# VU_Meter_1inchx3inches_V1_0.net
KiCad netlist of a schematic drawn in EAGLE
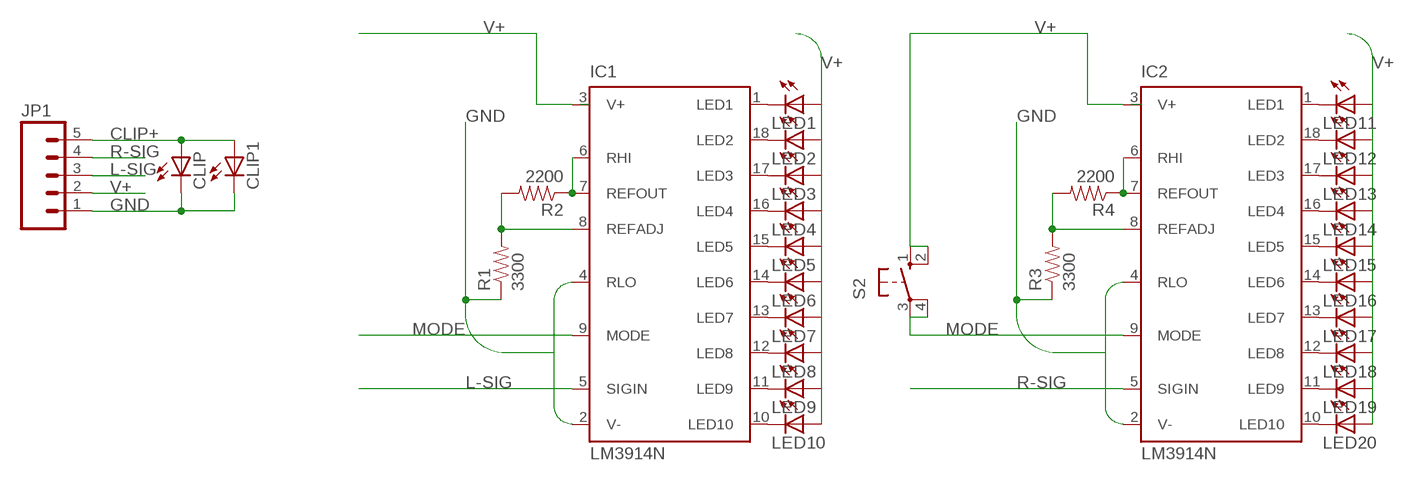
[diagram p0: schematic, sheet 1]

(export (version "E")
  (design (tool "Eeschema 10.0.6"))
  (components
    (comp (ref "CLIP")
      (value "LED5MM")
      (footprint "eagle-import:LED5MM")
      (libsource (lib "eagle-import") (part "LED5MM"))
    )
    (comp (ref "CLIP1")
      (value "LED5MM")
      (footprint "eagle-import:LED5MM")
      (libsource (lib "eagle-import") (part "LED5MM"))
    )
    (comp (ref "IC1")
      (value "LM3914N")
      (footprint "eagle-import:DIL18")
      (libsource (lib "eagle-import") (part "LM391N4"))
    )
    (comp (ref "IC2")
      (value "LM3914N")
      (footprint "eagle-import:DIL18")
      (libsource (lib "eagle-import") (part "LM391N4"))
    )
    (comp (ref "JP1")
      (value "M05SMD2")
      (footprint "eagle-import:1X05-1MM-RA")
      (libsource (lib "eagle-import") (part "M05SMD2"))
    )
    (comp (ref "LED1")
      (value "LED5MM")
      (footprint "eagle-import:LED5MM")
      (libsource (lib "eagle-import") (part "LED5MM"))
    )
    (comp (ref "LED2")
      (value "LED5MM")
      (footprint "eagle-import:LED5MM")
      (libsource (lib "eagle-import") (part "LED5MM"))
    )
    (comp (ref "LED3")
      (value "LED5MM")
      (footprint "eagle-import:LED5MM")
      (libsource (lib "eagle-import") (part "LED5MM"))
    )
    (comp (ref "LED4")
      (value "LED5MM")
      (footprint "eagle-import:LED5MM")
      (libsource (lib "eagle-import") (part "LED5MM"))
    )
    (comp (ref "LED5")
      (value "LED5MM")
      (footprint "eagle-import:LED5MM")
      (libsource (lib "eagle-import") (part "LED5MM"))
    )
    (comp (ref "LED6")
      (value "LED5MM")
      (footprint "eagle-import:LED5MM")
      (libsource (lib "eagle-import") (part "LED5MM"))
    )
    (comp (ref "LED7")
      (value "LED5MM")
      (footprint "eagle-import:LED5MM")
      (libsource (lib "eagle-import") (part "LED5MM"))
    )
    (comp (ref "LED8")
      (value "LED5MM")
      (footprint "eagle-import:LED5MM")
      (libsource (lib "eagle-import") (part "LED5MM"))
    )
    (comp (ref "LED9")
      (value "LED5MM")
      (footprint "eagle-import:LED5MM")
      (libsource (lib "eagle-import") (part "LED5MM"))
    )
    (comp (ref "LED10")
      (value "LED5MM")
      (footprint "eagle-import:LED5MM")
      (libsource (lib "eagle-import") (part "LED5MM"))
    )
    (comp (ref "LED11")
      (value "LED5MM")
      (footprint "eagle-import:LED5MM")
      (libsource (lib "eagle-import") (part "LED5MM"))
    )
    (comp (ref "LED12")
      (value "LED5MM")
      (footprint "eagle-import:LED5MM")
      (libsource (lib "eagle-import") (part "LED5MM"))
    )
    (comp (ref "LED13")
      (value "LED5MM")
      (footprint "eagle-import:LED5MM")
      (libsource (lib "eagle-import") (part "LED5MM"))
    )
    (comp (ref "LED14")
      (value "LED5MM")
      (footprint "eagle-import:LED5MM")
      (libsource (lib "eagle-import") (part "LED5MM"))
    )
    (comp (ref "LED15")
      (value "LED5MM")
      (footprint "eagle-import:LED5MM")
      (libsource (lib "eagle-import") (part "LED5MM"))
    )
    (comp (ref "LED16")
      (value "LED5MM")
      (footprint "eagle-import:LED5MM")
      (libsource (lib "eagle-import") (part "LED5MM"))
    )
    (comp (ref "LED17")
      (value "LED5MM")
      (footprint "eagle-import:LED5MM")
      (libsource (lib "eagle-import") (part "LED5MM"))
    )
    (comp (ref "LED18")
      (value "LED5MM")
      (footprint "eagle-import:LED5MM")
      (libsource (lib "eagle-import") (part "LED5MM"))
    )
    (comp (ref "LED19")
      (value "LED5MM")
      (footprint "eagle-import:LED5MM")
      (libsource (lib "eagle-import") (part "LED5MM"))
    )
    (comp (ref "LED20")
      (value "LED5MM")
      (footprint "eagle-import:LED5MM")
      (libsource (lib "eagle-import") (part "LED5MM"))
    )
    (comp (ref "R1")
      (value "3300")
      (footprint "eagle-import:AXIAL-0.4")
      (libsource (lib "eagle-import") (part "RESISTORPTH-1/4W"))
    )
    (comp (ref "R2")
      (value "2200")
      (footprint "eagle-import:AXIAL-0.4")
      (libsource (lib "eagle-import") (part "RESISTORPTH-1/4W"))
    )
    (comp (ref "R3")
      (value "3300")
      (footprint "eagle-import:AXIAL-0.4")
      (libsource (lib "eagle-import") (part "RESISTORPTH-1/4W"))
    )
    (comp (ref "R4")
      (value "2200")
      (footprint "eagle-import:AXIAL-0.4")
      (libsource (lib "eagle-import") (part "RESISTORPTH-1/4W"))
    )
    (comp (ref "S2")
      (value "10-XX")
      (footprint "eagle-import:B3F-10XX")
      (fields (field (name "MPN") "B3F-1000"))
      (libsource (lib "eagle-import") (part "10-XX"))
    )
  )
  (nets
    (net (code "1") (name "/CLIP+") (class "Default")
      (node (ref "CLIP") (pin "A") (pinfunction "A_A") (pintype "passive"))
      (node (ref "CLIP1") (pin "A") (pinfunction "A_A") (pintype "passive"))
      (node (ref "JP1") (pin "5") (pinfunction "5_5") (pintype "passive"))
    )
    (net (code "2") (name "/GND") (class "Default")
      (node (ref "CLIP") (pin "K") (pinfunction "C_K") (pintype "passive"))
      (node (ref "CLIP1") (pin "K") (pinfunction "C_K") (pintype "passive"))
      (node (ref "IC1") (pin "2") (pinfunction "V-_2") (pintype "power_in"))
      (node (ref "IC1") (pin "4") (pinfunction "RLO_4") (pintype "input"))
      (node (ref "IC2") (pin "2") (pinfunction "V-_2") (pintype "power_in"))
      (node (ref "IC2") (pin "4") (pinfunction "RLO_4") (pintype "input"))
      (node (ref "JP1") (pin "1") (pinfunction "1_1") (pintype "passive"))
      (node (ref "R1") (pin "P$1") (pinfunction "1_P$1") (pintype "passive"))
      (node (ref "R3") (pin "P$1") (pinfunction "1_P$1") (pintype "passive"))
    )
    (net (code "3") (name "/L-SIG") (class "Default")
      (node (ref "IC1") (pin "5") (pinfunction "SIGIN_5") (pintype "input"))
      (node (ref "JP1") (pin "3") (pinfunction "3_3") (pintype "passive"))
    )
    (net (code "4") (name "/MODE") (class "Default")
      (node (ref "IC1") (pin "9") (pinfunction "MODE_9") (pintype "input"))
      (node (ref "IC2") (pin "9") (pinfunction "MODE_9") (pintype "input"))
      (node (ref "S2") (pin "3") (pinfunction "P_3") (pintype "passive"))
      (node (ref "S2") (pin "4") (pinfunction "P1_4") (pintype "passive"))
    )
    (net (code "5") (name "/R-SIG") (class "Default")
      (node (ref "IC2") (pin "5") (pinfunction "SIGIN_5") (pintype "input"))
      (node (ref "JP1") (pin "4") (pinfunction "4_4") (pintype "passive"))
    )
    (net (code "6") (name "/V+") (class "Default")
      (node (ref "IC1") (pin "3") (pinfunction "V+_3") (pintype "power_in"))
      (node (ref "IC2") (pin "3") (pinfunction "V+_3") (pintype "power_in"))
      (node (ref "JP1") (pin "2") (pinfunction "2_2") (pintype "passive"))
      (node (ref "LED1") (pin "A") (pinfunction "A_A") (pintype "passive"))
      (node (ref "LED10") (pin "A") (pinfunction "A_A") (pintype "passive"))
      (node (ref "LED11") (pin "A") (pinfunction "A_A") (pintype "passive"))
      (node (ref "LED12") (pin "A") (pinfunction "A_A") (pintype "passive"))
      (node (ref "LED13") (pin "A") (pinfunction "A_A") (pintype "passive"))
      (node (ref "LED14") (pin "A") (pinfunction "A_A") (pintype "passive"))
      (node (ref "LED15") (pin "A") (pinfunction "A_A") (pintype "passive"))
      (node (ref "LED16") (pin "A") (pinfunction "A_A") (pintype "passive"))
      (node (ref "LED17") (pin "A") (pinfunction "A_A") (pintype "passive"))
      (node (ref "LED18") (pin "A") (pinfunction "A_A") (pintype "passive"))
      (node (ref "LED19") (pin "A") (pinfunction "A_A") (pintype "passive"))
      (node (ref "LED2") (pin "A") (pinfunction "A_A") (pintype "passive"))
      (node (ref "LED20") (pin "A") (pinfunction "A_A") (pintype "passive"))
      (node (ref "LED3") (pin "A") (pinfunction "A_A") (pintype "passive"))
      (node (ref "LED4") (pin "A") (pinfunction "A_A") (pintype "passive"))
      (node (ref "LED5") (pin "A") (pinfunction "A_A") (pintype "passive"))
      (node (ref "LED6") (pin "A") (pinfunction "A_A") (pintype "passive"))
      (node (ref "LED7") (pin "A") (pinfunction "A_A") (pintype "passive"))
      (node (ref "LED8") (pin "A") (pinfunction "A_A") (pintype "passive"))
      (node (ref "LED9") (pin "A") (pinfunction "A_A") (pintype "passive"))
      (node (ref "S2") (pin "1") (pinfunction "S_1") (pintype "passive"))
      (node (ref "S2") (pin "2") (pinfunction "S1_2") (pintype "passive"))
    )
    (net (code "7") (name "Net-(IC1-LED1)") (class "Default")
      (node (ref "IC1") (pin "1") (pinfunction "LED1_1") (pintype "output"))
      (node (ref "LED1") (pin "K") (pinfunction "C_K") (pintype "passive"))
    )
    (net (code "8") (name "Net-(IC1-LED2)") (class "Default")
      (node (ref "IC1") (pin "18") (pinfunction "LED2_18") (pintype "output"))
      (node (ref "LED2") (pin "K") (pinfunction "C_K") (pintype "passive"))
    )
    (net (code "9") (name "Net-(IC1-LED3)") (class "Default")
      (node (ref "IC1") (pin "17") (pinfunction "LED3_17") (pintype "output"))
      (node (ref "LED3") (pin "K") (pinfunction "C_K") (pintype "passive"))
    )
    (net (code "10") (name "Net-(IC1-LED4)") (class "Default")
      (node (ref "IC1") (pin "16") (pinfunction "LED4_16") (pintype "output"))
      (node (ref "LED4") (pin "K") (pinfunction "C_K") (pintype "passive"))
    )
    (net (code "11") (name "Net-(IC1-LED5)") (class "Default")
      (node (ref "IC1") (pin "15") (pinfunction "LED5_15") (pintype "output"))
      (node (ref "LED5") (pin "K") (pinfunction "C_K") (pintype "passive"))
    )
    (net (code "12") (name "Net-(IC1-LED6)") (class "Default")
      (node (ref "IC1") (pin "14") (pinfunction "LED6_14") (pintype "output"))
      (node (ref "LED6") (pin "K") (pinfunction "C_K") (pintype "passive"))
    )
    (net (code "13") (name "Net-(IC1-LED7)") (class "Default")
      (node (ref "IC1") (pin "13") (pinfunction "LED7_13") (pintype "output"))
      (node (ref "LED7") (pin "K") (pinfunction "C_K") (pintype "passive"))
    )
    (net (code "14") (name "Net-(IC1-LED8)") (class "Default")
      (node (ref "IC1") (pin "12") (pinfunction "LED8_12") (pintype "output"))
      (node (ref "LED8") (pin "K") (pinfunction "C_K") (pintype "passive"))
    )
    (net (code "15") (name "Net-(IC1-LED9)") (class "Default")
      (node (ref "IC1") (pin "11") (pinfunction "LED9_11") (pintype "output"))
      (node (ref "LED9") (pin "K") (pinfunction "C_K") (pintype "passive"))
    )
    (net (code "16") (name "Net-(IC1-LED10)") (class "Default")
      (node (ref "IC1") (pin "10") (pinfunction "LED10_10") (pintype "output"))
      (node (ref "LED10") (pin "K") (pinfunction "C_K") (pintype "passive"))
    )
    (net (code "17") (name "Net-(IC1-REFADJ)") (class "Default")
      (node (ref "IC1") (pin "8") (pinfunction "REFADJ_8") (pintype "passive"))
      (node (ref "R1") (pin "P$2") (pinfunction "2_P$2") (pintype "passive"))
      (node (ref "R2") (pin "P$2") (pinfunction "2_P$2") (pintype "passive"))
    )
    (net (code "18") (name "Net-(IC1-REFOUT)") (class "Default")
      (node (ref "IC1") (pin "6") (pinfunction "RHI_6") (pintype "input"))
      (node (ref "IC1") (pin "7") (pinfunction "REFOUT_7") (pintype "output"))
      (node (ref "R2") (pin "P$1") (pinfunction "1_P$1") (pintype "passive"))
    )
    (net (code "19") (name "Net-(IC2-LED1)") (class "Default")
      (node (ref "IC2") (pin "1") (pinfunction "LED1_1") (pintype "output"))
      (node (ref "LED11") (pin "K") (pinfunction "C_K") (pintype "passive"))
    )
    (net (code "20") (name "Net-(IC2-LED2)") (class "Default")
      (node (ref "IC2") (pin "18") (pinfunction "LED2_18") (pintype "output"))
      (node (ref "LED12") (pin "K") (pinfunction "C_K") (pintype "passive"))
    )
    (net (code "21") (name "Net-(IC2-LED3)") (class "Default")
      (node (ref "IC2") (pin "17") (pinfunction "LED3_17") (pintype "output"))
      (node (ref "LED13") (pin "K") (pinfunction "C_K") (pintype "passive"))
    )
    (net (code "22") (name "Net-(IC2-LED4)") (class "Default")
      (node (ref "IC2") (pin "16") (pinfunction "LED4_16") (pintype "output"))
      (node (ref "LED14") (pin "K") (pinfunction "C_K") (pintype "passive"))
    )
    (net (code "23") (name "Net-(IC2-LED5)") (class "Default")
      (node (ref "IC2") (pin "15") (pinfunction "LED5_15") (pintype "output"))
      (node (ref "LED15") (pin "K") (pinfunction "C_K") (pintype "passive"))
    )
    (net (code "24") (name "Net-(IC2-LED6)") (class "Default")
      (node (ref "IC2") (pin "14") (pinfunction "LED6_14") (pintype "output"))
      (node (ref "LED16") (pin "K") (pinfunction "C_K") (pintype "passive"))
    )
    (net (code "25") (name "Net-(IC2-LED7)") (class "Default")
      (node (ref "IC2") (pin "13") (pinfunction "LED7_13") (pintype "output"))
      (node (ref "LED17") (pin "K") (pinfunction "C_K") (pintype "passive"))
    )
    (net (code "26") (name "Net-(IC2-LED8)") (class "Default")
      (node (ref "IC2") (pin "12") (pinfunction "LED8_12") (pintype "output"))
      (node (ref "LED18") (pin "K") (pinfunction "C_K") (pintype "passive"))
    )
    (net (code "27") (name "Net-(IC2-LED9)") (class "Default")
      (node (ref "IC2") (pin "11") (pinfunction "LED9_11") (pintype "output"))
      (node (ref "LED19") (pin "K") (pinfunction "C_K") (pintype "passive"))
    )
    (net (code "28") (name "Net-(IC2-LED10)") (class "Default")
      (node (ref "IC2") (pin "10") (pinfunction "LED10_10") (pintype "output"))
      (node (ref "LED20") (pin "K") (pinfunction "C_K") (pintype "passive"))
    )
    (net (code "29") (name "Net-(IC2-REFADJ)") (class "Default")
      (node (ref "IC2") (pin "8") (pinfunction "REFADJ_8") (pintype "passive"))
      (node (ref "R3") (pin "P$2") (pinfunction "2_P$2") (pintype "passive"))
      (node (ref "R4") (pin "P$2") (pinfunction "2_P$2") (pintype "passive"))
    )
    (net (code "30") (name "Net-(IC2-REFOUT)") (class "Default")
      (node (ref "IC2") (pin "6") (pinfunction "RHI_6") (pintype "input"))
      (node (ref "IC2") (pin "7") (pinfunction "REFOUT_7") (pintype "output"))
      (node (ref "R4") (pin "P$1") (pinfunction "1_P$1") (pintype "passive"))
    )
  )
)
